# Driver3.net
KiCad netlist of a schematic drawn in EAGLE
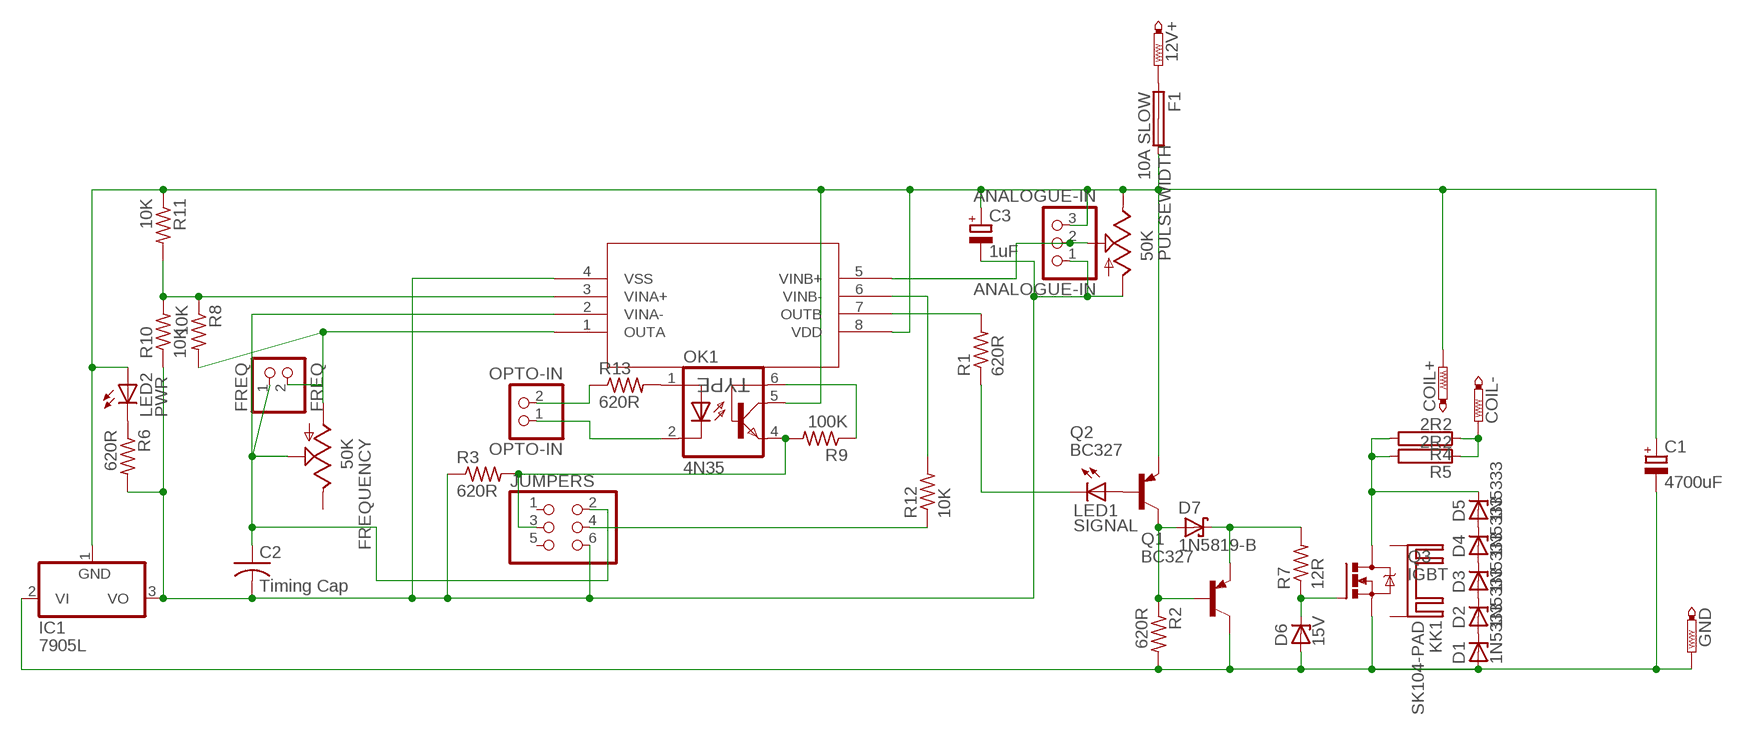
[diagram p0: schematic, sheet 1]

(export (version "E")
  (design (tool "Eeschema 10.0.6"))
  (components
    (comp (ref "12V+")
      (value "PTR1PAD1-20Y")
      (footprint "eagle-import:P1-20Y")
      (libsource (lib "eagle-import") (part "PTR1PAD1-20Y"))
    )
    (comp (ref "ANALOGUE-IN")
      (value "ANALOGUE-IN")
      (footprint "eagle-import:1X03")
      (libsource (lib "eagle-import") (part "PINHD-1X3"))
    )
    (comp (ref "C1")
      (value "4700uF")
      (footprint "eagle-import:E7,5-16")
      (libsource (lib "eagle-import") (part "CPOL-EUE7.5-16"))
    )
    (comp (ref "C2")
      (value "Timing Cap")
      (footprint "eagle-import:C050-025X075")
      (libsource (lib "eagle-import") (part "C-US050-025X075"))
    )
    (comp (ref "C3")
      (value "1uF")
      (footprint "eagle-import:E5-5")
      (libsource (lib "eagle-import") (part "CPOL-EUE5-5"))
    )
    (comp (ref "COIL+")
      (value "PTR1PAD1-20Y")
      (footprint "eagle-import:P1-20Y")
      (libsource (lib "eagle-import") (part "PTR1PAD1-20Y"))
    )
    (comp (ref "COIL-")
      (value "PTR1PAD1-20Y")
      (footprint "eagle-import:P1-20Y")
      (libsource (lib "eagle-import") (part "PTR1PAD1-20Y"))
    )
    (comp (ref "D1")
      (value "1N5333")
      (footprint "eagle-import:C1702-15")
      (libsource (lib "eagle-import") (part "1N5333"))
    )
    (comp (ref "D2")
      (value "1N5333")
      (footprint "eagle-import:C1702-15")
      (libsource (lib "eagle-import") (part "1N5333"))
    )
    (comp (ref "D3")
      (value "1N5333")
      (footprint "eagle-import:C1702-15")
      (libsource (lib "eagle-import") (part "1N5333"))
    )
    (comp (ref "D4")
      (value "1N5333")
      (footprint "eagle-import:C1702-15")
      (libsource (lib "eagle-import") (part "1N5333"))
    )
    (comp (ref "D5")
      (value "1N5333")
      (footprint "eagle-import:C1702-15")
      (libsource (lib "eagle-import") (part "1N5333"))
    )
    (comp (ref "D6")
      (value "15V")
      (footprint "eagle-import:DO34Z7")
      (libsource (lib "eagle-import") (part "BZV10"))
    )
    (comp (ref "D7")
      (value "1N5819-B")
      (footprint "eagle-import:DO41-7.6")
      (libsource (lib "eagle-import") (part "1N5819-B"))
    )
    (comp (ref "F1")
      (value "10A SLOW")
      (footprint "eagle-import:SHK20L")
      (libsource (lib "eagle-import") (part "SHK20L"))
    )
    (comp (ref "FREQ")
      (value "FREQ")
      (footprint "eagle-import:1X02")
      (libsource (lib "eagle-import") (part "PINHD-1X2"))
    )
    (comp (ref "FREQUENCY")
      (value "50K")
      (footprint "eagle-import:B25X")
      (libsource (lib "eagle-import") (part "TRIM_US-B25X"))
    )
    (comp (ref "GND")
      (value "PTR1PAD1-20Y")
      (footprint "eagle-import:P1-20Y")
      (libsource (lib "eagle-import") (part "PTR1PAD1-20Y"))
    )
    (comp (ref "IC1")
      (value "7905L")
      (footprint "eagle-import:TO92")
      (libsource (lib "eagle-import") (part "79L05"))
    )
    (comp (ref "JUMPERS")
      (value "PINHD-2X3")
      (footprint "eagle-import:2X03")
      (libsource (lib "eagle-import") (part "PINHD-2X3"))
    )
    (comp (ref "KK1")
      (value "SK104-PAD")
      (footprint "eagle-import:SK104-PAD")
      (libsource (lib "eagle-import") (part "SK104-PAD"))
    )
    (comp (ref "LED1")
      (value "SIGNAL")
      (footprint "eagle-import:LED3MM")
      (libsource (lib "eagle-import") (part "LED3MM"))
    )
    (comp (ref "LED2")
      (value "PWR")
      (footprint "eagle-import:LED3MM")
      (libsource (lib "eagle-import") (part "LED3MM"))
    )
    (comp (ref "OK1")
      (value "4N35")
      (footprint "eagle-import:DIL06")
      (fields (field (name "MF") "FAIRCHILD SEMICONDUCTOR"))
      (libsource (lib "eagle-import") (part "4N35"))
    )
    (comp (ref "OPTO-IN")
      (value "OPTO-IN")
      (footprint "eagle-import:1X02")
      (libsource (lib "eagle-import") (part "PINHD-1X2"))
    )
    (comp (ref "PULSEWIDTH")
      (value "50K")
      (footprint "eagle-import:B25X")
      (libsource (lib "eagle-import") (part "TRIM_US-B25X"))
    )
    (comp (ref "Q1")
      (value "BC327")
      (footprint "eagle-import:TO92")
      (libsource (lib "eagle-import") (part "BC327"))
    )
    (comp (ref "Q2")
      (value "BC327")
      (footprint "eagle-import:TO92")
      (libsource (lib "eagle-import") (part "BC327"))
    )
    (comp (ref "Q3")
      (value "IGBT")
      (footprint "eagle-import:TO220BV")
      (libsource (lib "eagle-import") (part "IRF740"))
    )
    (comp (ref "R1")
      (value "620R")
      (footprint "eagle-import:0204_7")
      (libsource (lib "eagle-import") (part "resistor_R-US_0204/7"))
    )
    (comp (ref "R2")
      (value "620R")
      (footprint "eagle-import:0204_7")
      (libsource (lib "eagle-import") (part "resistor_R-US_0204/7"))
    )
    (comp (ref "R3")
      (value "620R")
      (footprint "eagle-import:0204_7")
      (libsource (lib "eagle-import") (part "resistor_R-US_0204/7"))
    )
    (comp (ref "R4")
      (value "2R2")
      (footprint "eagle-import:HPS947")
      (libsource (lib "eagle-import") (part "RHPS947"))
    )
    (comp (ref "R5")
      (value "2R2")
      (footprint "eagle-import:HPS947")
      (libsource (lib "eagle-import") (part "RHPS947"))
    )
    (comp (ref "R6")
      (value "620R")
      (footprint "eagle-import:0204_7")
      (libsource (lib "eagle-import") (part "R-US_0204/7"))
    )
    (comp (ref "R7")
      (value "12R")
      (footprint "eagle-import:0204_7")
      (libsource (lib "eagle-import") (part "R-US_0204/7"))
    )
    (comp (ref "R8")
      (value "10K")
      (footprint "eagle-import:0204_7")
      (libsource (lib "eagle-import") (part "resistor_R-US_0204/7"))
    )
    (comp (ref "R9")
      (value "100K")
      (footprint "eagle-import:0204_7")
      (libsource (lib "eagle-import") (part "resistor_R-US_0204/7"))
    )
    (comp (ref "R10")
      (value "10K")
      (footprint "eagle-import:0204_7")
      (libsource (lib "eagle-import") (part "resistor_R-US_0204/7"))
    )
    (comp (ref "R11")
      (value "10K")
      (footprint "eagle-import:0204_7")
      (libsource (lib "eagle-import") (part "resistor_R-US_0204/7"))
    )
    (comp (ref "R12")
      (value "10K")
      (footprint "eagle-import:0204_7")
      (libsource (lib "eagle-import") (part "resistor_R-US_0204/7"))
    )
    (comp (ref "R13")
      (value "620R")
      (footprint "eagle-import:0204_7")
      (libsource (lib "eagle-import") (part "resistor_R-US_0204/7"))
    )
    (comp (ref "U$1")
      (value "MCP6542-X/P")
      (footprint "eagle-import:PDIP8_300MC")
      (libsource (lib "eagle-import") (part "MCP6542-X/P"))
    )
  )
  (nets
    (net (code "1") (name "Net-(12V+-PadTP)") (class "Default")
      (node (ref "12V+") (pin "TP") (pinfunction "TP_TP") (pintype "input"))
      (node (ref "F1") (pin "1A") (pinfunction "1A_1A") (pintype "passive"))
    )
    (net (code "2") (name "Net-(COIL--PadTP)") (class "Default")
      (node (ref "COIL-") (pin "TP") (pinfunction "TP_TP") (pintype "input"))
      (node (ref "R4") (pin "1") (pinfunction "1_1") (pintype "passive"))
      (node (ref "R5") (pin "1") (pinfunction "1_1") (pintype "passive"))
    )
    (net (code "3") (name "Net-(D1-PadC)") (class "Default")
      (node (ref "D1") (pin "C") (pinfunction "C_C") (pintype "passive"))
      (node (ref "D2") (pin "A") (pinfunction "A_A") (pintype "passive"))
    )
    (net (code "4") (name "Net-(D2-PadC)") (class "Default")
      (node (ref "D2") (pin "C") (pinfunction "C_C") (pintype "passive"))
      (node (ref "D3") (pin "A") (pinfunction "A_A") (pintype "passive"))
    )
    (net (code "5") (name "Net-(D3-PadC)") (class "Default")
      (node (ref "D3") (pin "C") (pinfunction "C_C") (pintype "passive"))
      (node (ref "D4") (pin "A") (pinfunction "A_A") (pintype "passive"))
    )
    (net (code "6") (name "Net-(D4-PadC)") (class "Default")
      (node (ref "D4") (pin "C") (pinfunction "C_C") (pintype "passive"))
      (node (ref "D5") (pin "A") (pinfunction "A_A") (pintype "passive"))
    )
    (net (code "7") (name "Net-(D5-PadC)") (class "Default")
      (node (ref "D5") (pin "C") (pinfunction "C_C") (pintype "passive"))
      (node (ref "Q3") (pin "D") (pinfunction "D_D") (pintype "passive"))
      (node (ref "R4") (pin "2") (pinfunction "2_2") (pintype "passive"))
      (node (ref "R5") (pin "2") (pinfunction "2_2") (pintype "passive"))
    )
    (net (code "8") (name "Net-(D6-PadC)") (class "Default")
      (node (ref "D6") (pin "C") (pinfunction "C_C") (pintype "passive"))
      (node (ref "Q3") (pin "G") (pinfunction "G_G") (pintype "passive"))
      (node (ref "R7") (pin "1") (pinfunction "1_1") (pintype "passive"))
    )
    (net (code "9") (name "Net-(IC1-GND)") (class "Default")
      (node (ref "ANALOGUE-IN") (pin "3") (pinfunction "3_3") (pintype "passive"))
      (node (ref "C1") (pin "+") (pinfunction "+_+") (pintype "passive"))
      (node (ref "C3") (pin "+") (pinfunction "+_+") (pintype "passive"))
      (node (ref "COIL+") (pin "TP") (pinfunction "TP_TP") (pintype "input"))
      (node (ref "F1") (pin "2A") (pinfunction "2A_2A") (pintype "passive"))
      (node (ref "IC1") (pin "1") (pinfunction "GND_1") (pintype "passive"))
      (node (ref "LED2") (pin "A") (pinfunction "A_A") (pintype "passive"))
      (node (ref "OK1") (pin "5") (pinfunction "COL_5") (pintype "passive"))
      (node (ref "PULSEWIDTH") (pin "E") (pinfunction "E_E") (pintype "passive"))
      (node (ref "Q2") (pin "1") (pinfunction "E_1") (pintype "passive"))
      (node (ref "R11") (pin "1") (pinfunction "1_1") (pintype "passive"))
      (node (ref "U$1") (pin "8") (pinfunction "VDD_8") (pintype "passive"))
    )
    (net (code "10") (name "Net-(IC1-VI)") (class "Default")
      (node (ref "C1") (pin "-") (pinfunction "-_-") (pintype "passive"))
      (node (ref "D1") (pin "A") (pinfunction "A_A") (pintype "passive"))
      (node (ref "D6") (pin "A") (pinfunction "A_A") (pintype "passive"))
      (node (ref "GND") (pin "TP") (pinfunction "TP_TP") (pintype "input"))
      (node (ref "IC1") (pin "2") (pinfunction "VI_2") (pintype "input"))
      (node (ref "Q1") (pin "3") (pinfunction "C_3") (pintype "passive"))
      (node (ref "Q3") (pin "S") (pinfunction "S_S") (pintype "passive"))
      (node (ref "R2") (pin "2") (pinfunction "2_2") (pintype "passive"))
    )
    (net (code "11") (name "Net-(IC1-VO)") (class "Default")
      (node (ref "ANALOGUE-IN") (pin "1") (pinfunction "1_1") (pintype "passive"))
      (node (ref "C2") (pin "2") (pinfunction "2_2") (pintype "passive"))
      (node (ref "C3") (pin "-") (pinfunction "-_-") (pintype "passive"))
      (node (ref "IC1") (pin "3") (pinfunction "VO_3") (pintype "passive"))
      (node (ref "JUMPERS") (pin "6") (pinfunction "6_6") (pintype "passive"))
      (node (ref "PULSEWIDTH") (pin "A") (pinfunction "A_A") (pintype "passive"))
      (node (ref "R10") (pin "1") (pinfunction "1_1") (pintype "passive"))
      (node (ref "R3") (pin "1") (pinfunction "1_1") (pintype "passive"))
      (node (ref "R6") (pin "2") (pinfunction "2_2") (pintype "passive"))
      (node (ref "U$1") (pin "4") (pinfunction "VSS_4") (pintype "passive"))
    )
    (net (code "12") (name "Net-(JUMPERS-Pad4)") (class "Default")
      (node (ref "JUMPERS") (pin "4") (pinfunction "4_4") (pintype "passive"))
      (node (ref "R12") (pin "1") (pinfunction "1_1") (pintype "passive"))
    )
    (net (code "13") (name "Net-(LED1-C)") (class "Default")
      (node (ref "LED1") (pin "K") (pinfunction "C_K") (pintype "passive"))
      (node (ref "R1") (pin "1") (pinfunction "1_1") (pintype "passive"))
    )
    (net (code "14") (name "Net-(LED2-C)") (class "Default")
      (node (ref "LED2") (pin "K") (pinfunction "C_K") (pintype "passive"))
      (node (ref "R6") (pin "1") (pinfunction "1_1") (pintype "passive"))
    )
    (net (code "15") (name "Net-(OK1-A)") (class "Default")
      (node (ref "OK1") (pin "1") (pinfunction "A_1") (pintype "passive"))
      (node (ref "R13") (pin "2") (pinfunction "2_2") (pintype "passive"))
    )
    (net (code "16") (name "Net-(OK1-BAS)") (class "Default")
      (node (ref "OK1") (pin "6") (pinfunction "BAS_6") (pintype "passive"))
      (node (ref "R9") (pin "1") (pinfunction "1_1") (pintype "passive"))
    )
    (net (code "17") (name "Net-(OK1-C)") (class "Default")
      (node (ref "OK1") (pin "2") (pinfunction "C_2") (pintype "passive"))
      (node (ref "OPTO-IN") (pin "1") (pinfunction "1_1") (pintype "passive"))
    )
    (net (code "18") (name "Net-(OK1-EMI)") (class "Default")
      (node (ref "JUMPERS") (pin "3") (pinfunction "3_3") (pintype "passive"))
      (node (ref "OK1") (pin "4") (pinfunction "EMI_4") (pintype "passive"))
      (node (ref "R3") (pin "2") (pinfunction "2_2") (pintype "passive"))
      (node (ref "R9") (pin "2") (pinfunction "2_2") (pintype "passive"))
    )
    (net (code "19") (name "Net-(OPTO-IN-Pad2)") (class "Default")
      (node (ref "OPTO-IN") (pin "2") (pinfunction "2_2") (pintype "passive"))
      (node (ref "R13") (pin "1") (pinfunction "1_1") (pintype "passive"))
    )
    (net (code "20") (name "Net-(Q1-B)") (class "Default")
      (node (ref "D7") (pin "A") (pinfunction "A_A") (pintype "passive"))
      (node (ref "Q1") (pin "2") (pinfunction "B_2") (pintype "passive"))
      (node (ref "Q2") (pin "3") (pinfunction "C_3") (pintype "passive"))
      (node (ref "R2") (pin "1") (pinfunction "1_1") (pintype "passive"))
    )
    (net (code "21") (name "Net-(Q1-E)") (class "Default")
      (node (ref "D7") (pin "C") (pinfunction "C_C") (pintype "passive"))
      (node (ref "Q1") (pin "1") (pinfunction "E_1") (pintype "passive"))
      (node (ref "R7") (pin "2") (pinfunction "2_2") (pintype "passive"))
    )
    (net (code "22") (name "Net-(Q2-B)") (class "Default")
      (node (ref "LED1") (pin "A") (pinfunction "A_A") (pintype "passive"))
      (node (ref "Q2") (pin "2") (pinfunction "B_2") (pintype "passive"))
    )
    (net (code "23") (name "Net-(U$1-OUTA)") (class "Default")
      (node (ref "FREQ") (pin "2") (pinfunction "2_2") (pintype "passive"))
      (node (ref "FREQUENCY") (pin "A") (pinfunction "A_A") (pintype "passive"))
      (node (ref "R8") (pin "2") (pinfunction "2_2") (pintype "passive"))
      (node (ref "U$1") (pin "1") (pinfunction "OUTA_1") (pintype "passive"))
    )
    (net (code "24") (name "Net-(U$1-OUTB)") (class "Default")
      (node (ref "R1") (pin "2") (pinfunction "2_2") (pintype "passive"))
      (node (ref "U$1") (pin "7") (pinfunction "OUTB_7") (pintype "passive"))
    )
    (net (code "25") (name "Net-(U$1-VINA+)") (class "Default")
      (node (ref "R10") (pin "2") (pinfunction "2_2") (pintype "passive"))
      (node (ref "R11") (pin "2") (pinfunction "2_2") (pintype "passive"))
      (node (ref "R8") (pin "1") (pinfunction "1_1") (pintype "passive"))
      (node (ref "U$1") (pin "3") (pinfunction "VINA+_3") (pintype "passive"))
    )
    (net (code "26") (name "Net-(U$1-VINA-)") (class "Default")
      (node (ref "C2") (pin "1") (pinfunction "1_1") (pintype "passive"))
      (node (ref "FREQ") (pin "1") (pinfunction "1_1") (pintype "passive"))
      (node (ref "FREQUENCY") (pin "S") (pinfunction "S_S") (pintype "passive"))
      (node (ref "JUMPERS") (pin "2") (pinfunction "2_2") (pintype "passive"))
      (node (ref "U$1") (pin "2") (pinfunction "VINA-_2") (pintype "passive"))
    )
    (net (code "27") (name "Net-(U$1-VINB+)") (class "Default")
      (node (ref "ANALOGUE-IN") (pin "2") (pinfunction "2_2") (pintype "passive"))
      (node (ref "PULSEWIDTH") (pin "S") (pinfunction "S_S") (pintype "passive"))
      (node (ref "U$1") (pin "5") (pinfunction "VINB+_5") (pintype "passive"))
    )
    (net (code "28") (name "Net-(U$1-VINB-)") (class "Default")
      (node (ref "R12") (pin "2") (pinfunction "2_2") (pintype "passive"))
      (node (ref "U$1") (pin "6") (pinfunction "VINB-_6") (pintype "passive"))
    )
    (net (code "29") (name "unconnected-(F1-Pad1B)") (class "Default")
      (node (ref "F1") (pin "1B") (pinfunction "1B_1B") (pintype "passive"))
    )
    (net (code "30") (name "unconnected-(F1-Pad2B)") (class "Default")
      (node (ref "F1") (pin "2B") (pinfunction "2B_2B") (pintype "passive"))
    )
    (net (code "31") (name "unconnected-(FREQUENCY-PadE)") (class "Default")
      (node (ref "FREQUENCY") (pin "E") (pinfunction "E_E") (pintype "passive"))
    )
    (net (code "32") (name "unconnected-(JUMPERS-Pad1)") (class "Default")
      (node (ref "JUMPERS") (pin "1") (pinfunction "1_1") (pintype "passive"))
    )
    (net (code "33") (name "unconnected-(JUMPERS-Pad5)") (class "Default")
      (node (ref "JUMPERS") (pin "5") (pinfunction "5_5") (pintype "passive"))
    )
    (net (code "34") (name "unconnected-(KK1-K-PadK1)") (class "Default")
      (node (ref "KK1") (pin "K1") (pinfunction "K_K1") (pintype "passive"))
    )
    (net (code "35") (name "unconnected-(KK1-K-PadK2)") (class "Default")
      (node (ref "KK1") (pin "K2") (pinfunction "K_K2") (pintype "passive"))
    )
  )
)
